# Power_stage.net
KiCad netlist of a schematic drawn in Altium Designer
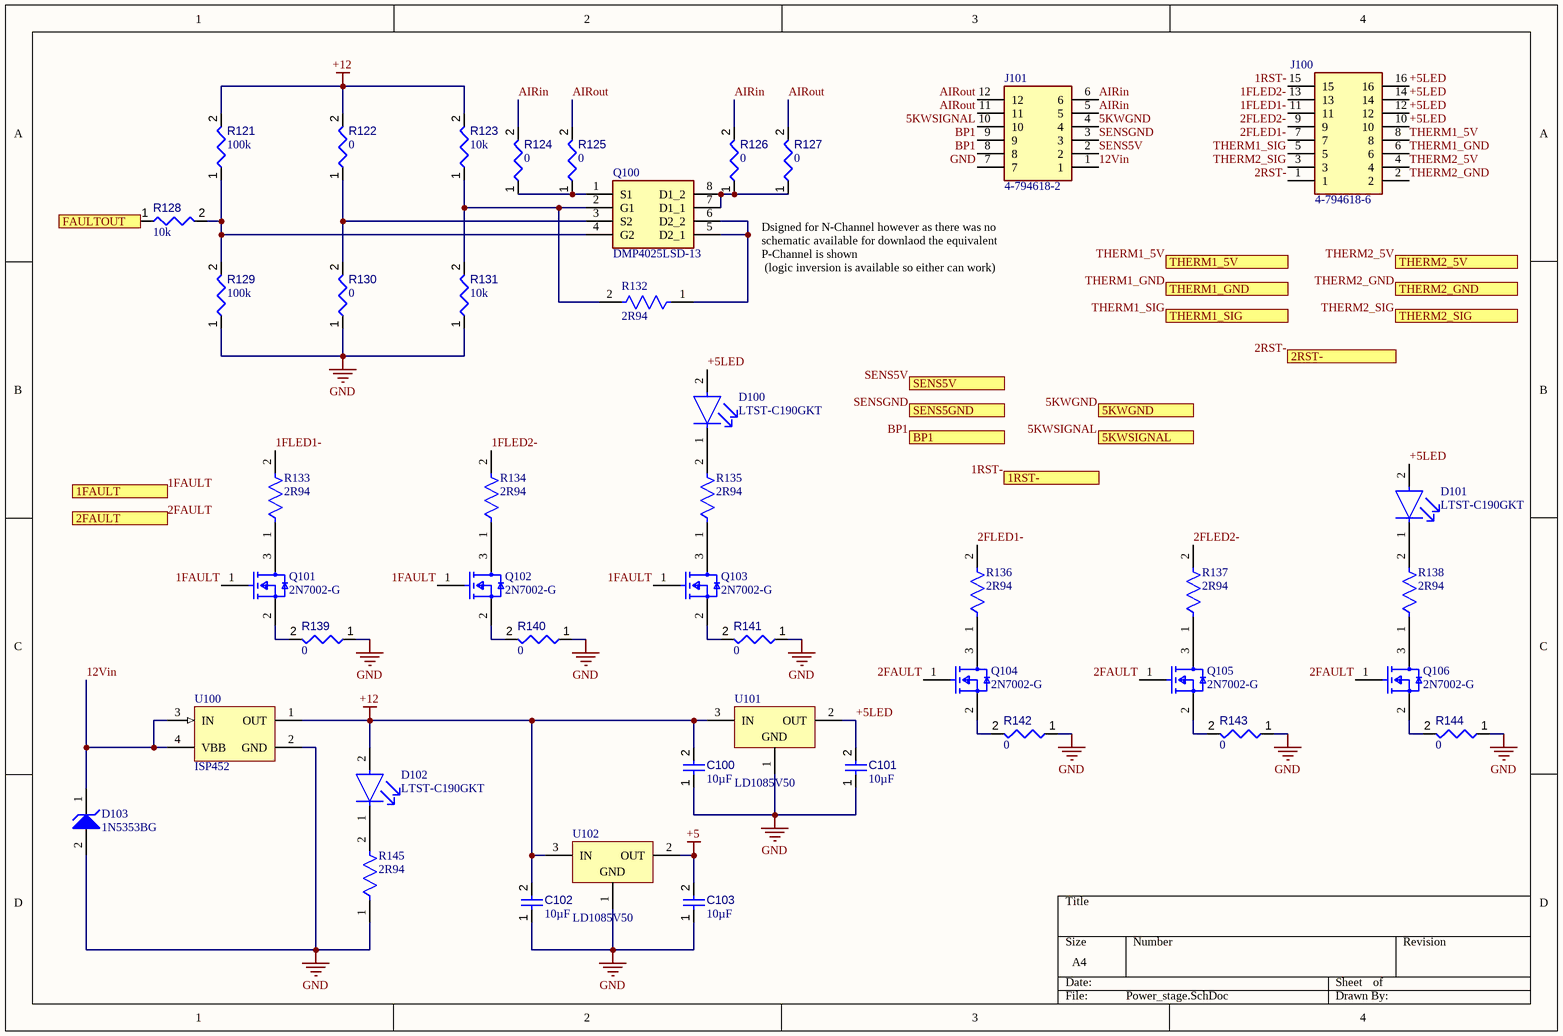
[diagram p0: Power_stage.SchDoc]

(export (version "E")
  (design (tool "Eeschema 10.0.6"))
  (components
    (comp (ref "C100")
      (value "10µF")
      (footprint "CAPC0805(2012)145_L")
      (description "Chip Capacitor, 10µF +/-20%, 25V, 0805, Thickness 1.45 mm")
      (fields (field (name "TOLERANCE") "10%") (field (name "Comment") "Capacitor 10µF +/-20% 25V 0805"))
      (libsource (lib "UNSW Redback Racing") (part "CAP-NP-2"))
    )
    (comp (ref "C101")
      (value "10µF")
      (footprint "CAPC0805(2012)145_L")
      (description "Chip Capacitor, 10µF +/-20%, 25V, 0805, Thickness 1.45 mm")
      (fields (field (name "TOLERANCE") "10%") (field (name "Comment") "Capacitor 10µF +/-20% 25V 0805"))
      (libsource (lib "UNSW Redback Racing") (part "CAP-NP-2"))
    )
    (comp (ref "C102")
      (value "10µF")
      (footprint "CAPC0805(2012)145_L")
      (description "Chip Capacitor, 10µF +/-20%, 25V, 0805, Thickness 1.45 mm")
      (fields (field (name "TOLERANCE") "10%") (field (name "Comment") "Capacitor 10µF +/-20% 25V 0805"))
      (libsource (lib "UNSW Redback Racing") (part "CAP-NP-2"))
    )
    (comp (ref "C103")
      (value "10µF")
      (footprint "CAPC0805(2012)145_L")
      (description "Chip Capacitor, 10µF +/-20%, 25V, 0805, Thickness 1.45 mm")
      (fields (field (name "TOLERANCE") "10%") (field (name "Comment") "Capacitor 10µF +/-20% 25V 0805"))
      (libsource (lib "UNSW Redback Racing") (part "CAP-NP-2"))
    )
    (comp (ref "D100")
      (value "LTST-C190GKT")
      (footprint "FP-LTST-C190GKT-MFG")
      (description "LED GREEN CLEAR CHIP SMD")
      (fields (field (name "VOLTAGE") "2V"))
      (libsource (lib "Altium Content Vault") (part "8706943c75ba83719d021d2fdc84c58"))
    )
    (comp (ref "D101")
      (value "LTST-C190GKT")
      (footprint "FP-LTST-C190GKT-MFG")
      (description "LED GREEN CLEAR CHIP SMD")
      (fields (field (name "VOLTAGE") "2V"))
      (libsource (lib "Altium Content Vault") (part "8706943c75ba83719d021d2fdc84c58"))
    )
    (comp (ref "D102")
      (value "LTST-C190GKT")
      (footprint "FP-LTST-C190GKT-MFG")
      (description "LED GREEN CLEAR CHIP SMD")
      (fields (field (name "VOLTAGE") "2V"))
      (libsource (lib "Altium Content Vault") (part "8706943c75ba83719d021d2fdc84c58"))
    )
    (comp (ref "D103")
      (value "1N5353BG")
      (footprint "ONSC-SURMETIC40-2-017AA-01")
      (description "5 W Zener Voltage Regulator, 2-Pin Surmetic(TM) 40, Pb-Free, Bulk Box")
      (fields (field (name "MANUFACTURER") "On Semiconductor"))
      (libsource (lib "Altium Content Vault") (part "ONSC-K1A2-2"))
    )
    (comp (ref "J100")
      (value "4-794618-6")
      (footprint "SamacSys:47946186")
      (description "Connector")
      (fields (field (name "MOUSER PART NUMBER") "571-4-794618-6"))
      (libsource (lib "*") (part "4-794618-6"))
    )
    (comp (ref "J101")
      (value "4-794618-2")
      (footprint "SamacSys:47946182")
      (description "Connector")
      (fields (field (name "MOUSER PART NUMBER") "571-4-794618-2"))
      (libsource (lib "*") (part "4-794618-2"))
    )
    (comp (ref "Q100")
      (value "DMP4025LSD-13")
      (footprint "SamacSys:SOIC127P600X175-8N")
      (description "MOSFET (P-Channel)")
      (fields (field (name "MOUSER PART NUMBER") "621-DMP4025LSD-13"))
      (libsource (lib "*") (part "DMP4025LSD-13"))
    )
    (comp (ref "Q101")
      (value "2N7002-G")
      (footprint "FP-2N7002-G-IPC_C")
      (description "MOSFET N-CH 60V 0.115A SOT23-3")
      (fields
        (field (name "OCTOPART") "https://octopart.com/2n7002-g-microchip-47153309")
        (field (name "MANUFACTURER") "Microchip")
      )
      (libsource (lib "Altium Content Vault") (part "e719174c72bdd709d73c8feae40c216"))
    )
    (comp (ref "Q102")
      (value "2N7002-G")
      (footprint "FP-2N7002-G-IPC_C")
      (description "MOSFET N-CH 60V 0.115A SOT23-3")
      (fields
        (field (name "OCTOPART") "https://octopart.com/2n7002-g-microchip-47153309")
        (field (name "MANUFACTURER") "Microchip")
      )
      (libsource (lib "Altium Content Vault") (part "e719174c72bdd709d73c8feae40c216"))
    )
    (comp (ref "Q103")
      (value "2N7002-G")
      (footprint "FP-2N7002-G-IPC_C")
      (description "MOSFET N-CH 60V 0.115A SOT23-3")
      (fields
        (field (name "OCTOPART") "https://octopart.com/2n7002-g-microchip-47153309")
        (field (name "MANUFACTURER") "Microchip")
      )
      (libsource (lib "Altium Content Vault") (part "e719174c72bdd709d73c8feae40c216"))
    )
    (comp (ref "Q104")
      (value "2N7002-G")
      (footprint "FP-2N7002-G-IPC_C")
      (description "MOSFET N-CH 60V 0.115A SOT23-3")
      (fields
        (field (name "OCTOPART") "https://octopart.com/2n7002-g-microchip-47153309")
        (field (name "MANUFACTURER") "Microchip")
      )
      (libsource (lib "Altium Content Vault") (part "e719174c72bdd709d73c8feae40c216"))
    )
    (comp (ref "Q105")
      (value "2N7002-G")
      (footprint "FP-2N7002-G-IPC_C")
      (description "MOSFET N-CH 60V 0.115A SOT23-3")
      (fields
        (field (name "OCTOPART") "https://octopart.com/2n7002-g-microchip-47153309")
        (field (name "MANUFACTURER") "Microchip")
      )
      (libsource (lib "Altium Content Vault") (part "e719174c72bdd709d73c8feae40c216"))
    )
    (comp (ref "Q106")
      (value "2N7002-G")
      (footprint "FP-2N7002-G-IPC_C")
      (description "MOSFET N-CH 60V 0.115A SOT23-3")
      (fields
        (field (name "OCTOPART") "https://octopart.com/2n7002-g-microchip-47153309")
        (field (name "MANUFACTURER") "Microchip")
      )
      (libsource (lib "Altium Content Vault") (part "e719174c72bdd709d73c8feae40c216"))
    )
    (comp (ref "R121")
      (value "100k")
      (footprint "RESC1608X55X25ML10T15")
      (description "Chip Resistor, 100 KOhm, +/- 1%, 0.1 W, -55 to 155 degC, 0603 (1608 Metric)")
      (fields (field (name "TOLERANCE") "1%") (field (name "POWER") "100mW"))
      (libsource (lib "UNSW Redback Racing") (part "RES-2"))
    )
    (comp (ref "R122")
      (value "0")
      (footprint "RESC0603(1608)_L")
      (description "Jumper 0603 (1608 Metric)")
      (fields (field (name "Comment") "0R3J"))
      (libsource (lib "UNSW Redback Racing") (part "0R3J"))
    )
    (comp (ref "R123")
      (value "10k")
      (footprint "RESC1608X55X25ML10T15")
      (description "Chip Resistor, 10 KOhm, +/- 1%, 01 W, -55 to 155 degC, 0603 (1608 Metric)")
      (fields (field (name "POWER") "100mW") (field (name "TOLERANCE") "1%"))
      (libsource (lib "UNSW Redback Racing") (part "RES-2"))
    )
    (comp (ref "R124")
      (value "0")
      (footprint "RESC0603(1608)_L")
      (description "Jumper 0603 (1608 Metric)")
      (fields (field (name "Comment") "0R3J"))
      (libsource (lib "UNSW Redback Racing") (part "0R3J"))
    )
    (comp (ref "R125")
      (value "0")
      (footprint "RESC0603(1608)_L")
      (description "Jumper 0603 (1608 Metric)")
      (fields (field (name "Comment") "0R3J"))
      (libsource (lib "UNSW Redback Racing") (part "0R3J"))
    )
    (comp (ref "R126")
      (value "0")
      (footprint "RESC0603(1608)_L")
      (description "Jumper 0603 (1608 Metric)")
      (fields (field (name "Comment") "0R3J"))
      (libsource (lib "UNSW Redback Racing") (part "0R3J"))
    )
    (comp (ref "R127")
      (value "0")
      (footprint "RESC0603(1608)_L")
      (description "Jumper 0603 (1608 Metric)")
      (fields (field (name "Comment") "0R3J"))
      (libsource (lib "UNSW Redback Racing") (part "0R3J"))
    )
    (comp (ref "R128")
      (value "10k")
      (footprint "RESC1608X55X25ML10T15")
      (description "Chip Resistor, 10 KOhm, +/- 1%, 01 W, -55 to 155 degC, 0603 (1608 Metric)")
      (fields (field (name "POWER") "100mW") (field (name "TOLERANCE") "1%"))
      (libsource (lib "UNSW Redback Racing") (part "RES-2"))
    )
    (comp (ref "R129")
      (value "100k")
      (footprint "RESC1608X55X25ML10T15")
      (description "Chip Resistor, 100 KOhm, +/- 1%, 0.1 W, -55 to 155 degC, 0603 (1608 Metric)")
      (fields (field (name "TOLERANCE") "1%") (field (name "POWER") "100mW"))
      (libsource (lib "UNSW Redback Racing") (part "RES-2"))
    )
    (comp (ref "R130")
      (value "0")
      (footprint "RESC0603(1608)_L")
      (description "Jumper 0603 (1608 Metric)")
      (fields (field (name "Comment") "0R3J"))
      (libsource (lib "UNSW Redback Racing") (part "0R3J"))
    )
    (comp (ref "R131")
      (value "10k")
      (footprint "RESC1608X55X25ML10T15")
      (description "Chip Resistor, 10 KOhm, +/- 1%, 01 W, -55 to 155 degC, 0603 (1608 Metric)")
      (fields (field (name "POWER") "100mW") (field (name "TOLERANCE") "1%"))
      (libsource (lib "UNSW Redback Racing") (part "RES-2"))
    )
    (comp (ref "R132")
      (value "2R94")
      (footprint "FP-CPF0603-MFG")
      (description "RES SMD 2.94Ω 1% 1/16W 0603")
      (fields (field (name "MANUFACTURER PART NUMBER") "CPF0603F2R94C1") (field (name "TOLERANCE") "1%"))
      (libsource (lib "Altium Content Vault") (part "1029c3af85768c4190bb7ad29bc67b5"))
    )
    (comp (ref "R133")
      (value "2R94")
      (footprint "FP-CPF0603-MFG")
      (description "RES SMD 2.94Ω 1% 1/16W 0603")
      (fields (field (name "MANUFACTURER PART NUMBER") "CPF0603F2R94C1") (field (name "TOLERANCE") "1%"))
      (libsource (lib "Altium Content Vault") (part "1029c3af85768c4190bb7ad29bc67b5"))
    )
    (comp (ref "R134")
      (value "2R94")
      (footprint "FP-CPF0603-MFG")
      (description "RES SMD 2.94Ω 1% 1/16W 0603")
      (fields (field (name "MANUFACTURER PART NUMBER") "CPF0603F2R94C1") (field (name "TOLERANCE") "1%"))
      (libsource (lib "Altium Content Vault") (part "1029c3af85768c4190bb7ad29bc67b5"))
    )
    (comp (ref "R135")
      (value "2R94")
      (footprint "FP-CPF0603-MFG")
      (description "RES SMD 2.94Ω 1% 1/16W 0603")
      (fields (field (name "MANUFACTURER PART NUMBER") "CPF0603F2R94C1") (field (name "TOLERANCE") "1%"))
      (libsource (lib "Altium Content Vault") (part "1029c3af85768c4190bb7ad29bc67b5"))
    )
    (comp (ref "R136")
      (value "2R94")
      (footprint "FP-CPF0603-MFG")
      (description "RES SMD 2.94Ω 1% 1/16W 0603")
      (fields (field (name "MANUFACTURER PART NUMBER") "CPF0603F2R94C1") (field (name "TOLERANCE") "1%"))
      (libsource (lib "Altium Content Vault") (part "1029c3af85768c4190bb7ad29bc67b5"))
    )
    (comp (ref "R137")
      (value "2R94")
      (footprint "FP-CPF0603-MFG")
      (description "RES SMD 2.94Ω 1% 1/16W 0603")
      (fields (field (name "MANUFACTURER PART NUMBER") "CPF0603F2R94C1") (field (name "TOLERANCE") "1%"))
      (libsource (lib "Altium Content Vault") (part "1029c3af85768c4190bb7ad29bc67b5"))
    )
    (comp (ref "R138")
      (value "2R94")
      (footprint "FP-CPF0603-MFG")
      (description "RES SMD 2.94Ω 1% 1/16W 0603")
      (fields (field (name "MANUFACTURER PART NUMBER") "CPF0603F2R94C1") (field (name "TOLERANCE") "1%"))
      (libsource (lib "Altium Content Vault") (part "1029c3af85768c4190bb7ad29bc67b5"))
    )
    (comp (ref "R139")
      (value "0")
      (footprint "RESC0603(1608)_L")
      (description "Jumper 0603 (1608 Metric)")
      (fields (field (name "Comment") "0R3J"))
      (libsource (lib "UNSW Redback Racing") (part "0R3J"))
    )
    (comp (ref "R140")
      (value "0")
      (footprint "RESC0603(1608)_L")
      (description "Jumper 0603 (1608 Metric)")
      (fields (field (name "Comment") "0R3J"))
      (libsource (lib "UNSW Redback Racing") (part "0R3J"))
    )
    (comp (ref "R141")
      (value "0")
      (footprint "RESC0603(1608)_L")
      (description "Jumper 0603 (1608 Metric)")
      (fields (field (name "Comment") "0R3J"))
      (libsource (lib "UNSW Redback Racing") (part "0R3J"))
    )
    (comp (ref "R142")
      (value "0")
      (footprint "RESC0603(1608)_L")
      (description "Jumper 0603 (1608 Metric)")
      (fields (field (name "Comment") "0R3J"))
      (libsource (lib "UNSW Redback Racing") (part "0R3J"))
    )
    (comp (ref "R143")
      (value "0")
      (footprint "RESC0603(1608)_L")
      (description "Jumper 0603 (1608 Metric)")
      (fields (field (name "Comment") "0R3J"))
      (libsource (lib "UNSW Redback Racing") (part "0R3J"))
    )
    (comp (ref "R144")
      (value "0")
      (footprint "RESC0603(1608)_L")
      (description "Jumper 0603 (1608 Metric)")
      (fields (field (name "Comment") "0R3J"))
      (libsource (lib "UNSW Redback Racing") (part "0R3J"))
    )
    (comp (ref "R145")
      (value "2R94")
      (footprint "FP-CPF0603-MFG")
      (description "RES SMD 2.94Ω 1% 1/16W 0603")
      (fields (field (name "MANUFACTURER PART NUMBER") "CPF0603F2R94C1") (field (name "TOLERANCE") "1%"))
      (libsource (lib "Altium Content Vault") (part "1029c3af85768c4190bb7ad29bc67b5"))
    )
    (comp (ref "U100")
      (value "ISP452")
      (footprint "INF-SOT223_L")
      (fields (field (name "MANUFACTURER") "Infineon"))
      (libsource (lib "Altium Content Vault") (part "INF-ISP452-SOT223-4"))
    )
    (comp (ref "U101")
      (value "LD1085V50")
      (footprint "TO220")
      (description "3A, Low Drop Positive Voltage Regulator, 5V, 3-Pin TO-220")
      (libsource (lib "Altium Content Vault") (part "PM-REG-LD1085-SIL3"))
    )
    (comp (ref "U102")
      (value "LD1085V50")
      (footprint "TO220")
      (description "3A, Low Drop Positive Voltage Regulator, 5V, 3-Pin TO-220")
      (libsource (lib "Altium Content Vault") (part "PM-REG-LD1085-SIL3"))
    )
  )
  (nets
    (net (code "1") (name "+5") (class "Default")
      (node (ref "C103") (pin "2") (pinfunction "2_2") (pintype "passive"))
      (node (ref "U102") (pin "2") (pinfunction "OUT_2") (pintype "power_in"))
    )
    (net (code "2") (name "+12") (class "Default")
      (node (ref "C100") (pin "2") (pinfunction "2_2") (pintype "passive"))
      (node (ref "C102") (pin "2") (pinfunction "2_2") (pintype "passive"))
      (node (ref "D102") (pin "2") (pinfunction "A_2") (pintype "passive"))
      (node (ref "R121") (pin "2") (pinfunction "2_2") (pintype "passive"))
      (node (ref "R122") (pin "2") (pinfunction "2_2") (pintype "passive"))
      (node (ref "R123") (pin "2") (pinfunction "2_2") (pintype "passive"))
      (node (ref "U100") (pin "1") (pinfunction "OUT_1") (pintype "power_in"))
      (node (ref "U101") (pin "3") (pinfunction "IN_3") (pintype "power_in"))
      (node (ref "U102") (pin "3") (pinfunction "IN_3") (pintype "power_in"))
    )
    (net (code "3") (name "/+5LED") (class "Default")
      (node (ref "C101") (pin "2") (pinfunction "2_2") (pintype "passive"))
      (node (ref "D100") (pin "2") (pinfunction "A_2") (pintype "passive"))
      (node (ref "D101") (pin "2") (pinfunction "A_2") (pintype "passive"))
      (node (ref "J100") (pin "10") (pinfunction "10_10") (pintype "passive"))
      (node (ref "J100") (pin "12") (pinfunction "12_12") (pintype "passive"))
      (node (ref "J100") (pin "14") (pinfunction "14_14") (pintype "passive"))
      (node (ref "J100") (pin "16") (pinfunction "16_16") (pintype "passive"))
      (node (ref "U101") (pin "2") (pinfunction "OUT_2") (pintype "power_in"))
    )
    (net (code "4") (name "/1FAULT") (class "Default")
      (node (ref "Q101") (pin "1") (pinfunction "GATE_1") (pintype "passive"))
      (node (ref "Q102") (pin "1") (pinfunction "GATE_1") (pintype "passive"))
      (node (ref "Q103") (pin "1") (pinfunction "GATE_1") (pintype "passive"))
    )
    (net (code "5") (name "/1FLED1-") (class "Default")
      (node (ref "J100") (pin "11") (pinfunction "11_11") (pintype "passive"))
      (node (ref "R133") (pin "2") (pinfunction "2_2") (pintype "passive"))
    )
    (net (code "6") (name "/1FLED2-") (class "Default")
      (node (ref "J100") (pin "13") (pinfunction "13_13") (pintype "passive"))
      (node (ref "R134") (pin "2") (pinfunction "2_2") (pintype "passive"))
    )
    (net (code "7") (name "/1RST-") (class "Default")
      (node (ref "J100") (pin "15") (pinfunction "15_15") (pintype "passive"))
    )
    (net (code "8") (name "/2FAULT") (class "Default")
      (node (ref "Q104") (pin "1") (pinfunction "GATE_1") (pintype "passive"))
      (node (ref "Q105") (pin "1") (pinfunction "GATE_1") (pintype "passive"))
      (node (ref "Q106") (pin "1") (pinfunction "GATE_1") (pintype "passive"))
    )
    (net (code "9") (name "/2FLED1-") (class "Default")
      (node (ref "J100") (pin "7") (pinfunction "7_7") (pintype "passive"))
      (node (ref "R136") (pin "2") (pinfunction "2_2") (pintype "passive"))
    )
    (net (code "10") (name "/2FLED2-") (class "Default")
      (node (ref "J100") (pin "9") (pinfunction "9_9") (pintype "passive"))
      (node (ref "R137") (pin "2") (pinfunction "2_2") (pintype "passive"))
    )
    (net (code "11") (name "/2RST-") (class "Default")
      (node (ref "J100") (pin "1") (pinfunction "1_1") (pintype "passive"))
    )
    (net (code "12") (name "/5KWGND") (class "Default")
      (node (ref "J101") (pin "4") (pinfunction "4_4") (pintype "passive"))
    )
    (net (code "13") (name "/5KWSIGNAL") (class "Default")
      (node (ref "J101") (pin "10") (pinfunction "10_10") (pintype "passive"))
    )
    (net (code "14") (name "/12Vin") (class "Default")
      (node (ref "D103") (pin "1") (pinfunction "K_1") (pintype "passive"))
      (node (ref "J101") (pin "1") (pinfunction "1_1") (pintype "passive"))
      (node (ref "U100") (pin "3") (pinfunction "IN_3") (pintype "input"))
      (node (ref "U100") (pin "4") (pinfunction "VBB_4") (pintype "power_in"))
    )
    (net (code "15") (name "/AIRin") (class "Default")
      (node (ref "J101") (pin "5") (pinfunction "5_5") (pintype "passive"))
      (node (ref "J101") (pin "6") (pinfunction "6_6") (pintype "passive"))
      (node (ref "R124") (pin "2") (pinfunction "2_2") (pintype "passive"))
      (node (ref "R126") (pin "2") (pinfunction "2_2") (pintype "passive"))
    )
    (net (code "16") (name "/AIRout") (class "Default")
      (node (ref "J101") (pin "11") (pinfunction "11_11") (pintype "passive"))
      (node (ref "J101") (pin "12") (pinfunction "12_12") (pintype "passive"))
      (node (ref "R125") (pin "2") (pinfunction "2_2") (pintype "passive"))
      (node (ref "R127") (pin "2") (pinfunction "2_2") (pintype "passive"))
    )
    (net (code "17") (name "/BP1") (class "Default")
      (node (ref "J101") (pin "8") (pinfunction "8_8") (pintype "passive"))
      (node (ref "J101") (pin "9") (pinfunction "9_9") (pintype "passive"))
    )
    (net (code "18") (name "/FAULTOUT") (class "Default")
      (node (ref "R128") (pin "1") (pinfunction "1_1") (pintype "passive"))
    )
    (net (code "20") (name "/SENS5V") (class "Default")
      (node (ref "J101") (pin "2") (pinfunction "2_2") (pintype "passive"))
    )
    (net (code "21") (name "/SENSGND") (class "Default")
      (node (ref "J101") (pin "3") (pinfunction "3_3") (pintype "passive"))
    )
    (net (code "22") (name "/THERM1_5V") (class "Default")
      (node (ref "J100") (pin "8") (pinfunction "8_8") (pintype "passive"))
    )
    (net (code "23") (name "/THERM1_GND") (class "Default")
      (node (ref "J100") (pin "6") (pinfunction "6_6") (pintype "passive"))
    )
    (net (code "24") (name "/THERM1_SIG") (class "Default")
      (node (ref "J100") (pin "5") (pinfunction "5_5") (pintype "passive"))
    )
    (net (code "25") (name "/THERM2_5V") (class "Default")
      (node (ref "J100") (pin "4") (pinfunction "4_4") (pintype "passive"))
    )
    (net (code "26") (name "/THERM2_GND") (class "Default")
      (node (ref "J100") (pin "2") (pinfunction "2_2") (pintype "passive"))
    )
    (net (code "27") (name "/THERM2_SIG") (class "Default")
      (node (ref "J100") (pin "3") (pinfunction "3_3") (pintype "passive"))
    )
    (net (code "28") (name "GND") (class "Default")
      (node (ref "C100") (pin "1") (pinfunction "1_1") (pintype "passive"))
      (node (ref "C101") (pin "1") (pinfunction "1_1") (pintype "passive"))
      (node (ref "C102") (pin "1") (pinfunction "1_1") (pintype "passive"))
      (node (ref "C103") (pin "1") (pinfunction "1_1") (pintype "passive"))
      (node (ref "D103") (pin "2") (pinfunction "A_2") (pintype "passive"))
      (node (ref "J101") (pin "7") (pinfunction "7_7") (pintype "passive"))
      (node (ref "R129") (pin "1") (pinfunction "1_1") (pintype "passive"))
      (node (ref "R130") (pin "1") (pinfunction "1_1") (pintype "passive"))
      (node (ref "R131") (pin "1") (pinfunction "1_1") (pintype "passive"))
      (node (ref "R139") (pin "1") (pinfunction "1_1") (pintype "passive"))
      (node (ref "R140") (pin "1") (pinfunction "1_1") (pintype "passive"))
      (node (ref "R141") (pin "1") (pinfunction "1_1") (pintype "passive"))
      (node (ref "R142") (pin "1") (pinfunction "1_1") (pintype "passive"))
      (node (ref "R143") (pin "1") (pinfunction "1_1") (pintype "passive"))
      (node (ref "R144") (pin "1") (pinfunction "1_1") (pintype "passive"))
      (node (ref "R145") (pin "1") (pinfunction "1_1") (pintype "passive"))
      (node (ref "U100") (pin "2") (pinfunction "GND_2") (pintype "power_in"))
      (node (ref "U101") (pin "1") (pinfunction "GND_1") (pintype "power_in"))
      (node (ref "U102") (pin "1") (pinfunction "GND_1") (pintype "power_in"))
    )
    (net (code "29") (name "Net-(D100-C)") (class "Default")
      (node (ref "D100") (pin "1") (pinfunction "C_1") (pintype "passive"))
      (node (ref "R135") (pin "2") (pinfunction "2_2") (pintype "passive"))
    )
    (net (code "30") (name "Net-(D101-C)") (class "Default")
      (node (ref "D101") (pin "1") (pinfunction "C_1") (pintype "passive"))
      (node (ref "R138") (pin "2") (pinfunction "2_2") (pintype "passive"))
    )
    (net (code "31") (name "Net-(D102-C)") (class "Default")
      (node (ref "D102") (pin "1") (pinfunction "C_1") (pintype "passive"))
      (node (ref "R145") (pin "2") (pinfunction "2_2") (pintype "passive"))
    )
    (net (code "32") (name "Net-(Q100-D1_1)") (class "Default")
      (node (ref "Q100") (pin "7") (pinfunction "D1_1_7") (pintype "passive"))
      (node (ref "Q100") (pin "8") (pinfunction "D1_2_8") (pintype "passive"))
      (node (ref "R126") (pin "1") (pinfunction "1_1") (pintype "passive"))
      (node (ref "R127") (pin "1") (pinfunction "1_1") (pintype "passive"))
    )
    (net (code "33") (name "Net-(Q100-D2_1)") (class "Default")
      (node (ref "Q100") (pin "5") (pinfunction "D2_1_5") (pintype "passive"))
      (node (ref "Q100") (pin "6") (pinfunction "D2_2_6") (pintype "passive"))
      (node (ref "R132") (pin "1") (pinfunction "1_1") (pintype "passive"))
    )
    (net (code "34") (name "Net-(Q100-G1)") (class "Default")
      (node (ref "Q100") (pin "2") (pinfunction "G1_2") (pintype "passive"))
      (node (ref "R123") (pin "1") (pinfunction "1_1") (pintype "passive"))
      (node (ref "R131") (pin "2") (pinfunction "2_2") (pintype "passive"))
      (node (ref "R132") (pin "2") (pinfunction "2_2") (pintype "passive"))
    )
    (net (code "35") (name "Net-(Q100-G2)") (class "Default")
      (node (ref "Q100") (pin "4") (pinfunction "G2_4") (pintype "passive"))
      (node (ref "R121") (pin "1") (pinfunction "1_1") (pintype "passive"))
      (node (ref "R128") (pin "2") (pinfunction "2_2") (pintype "passive"))
      (node (ref "R129") (pin "2") (pinfunction "2_2") (pintype "passive"))
    )
    (net (code "36") (name "Net-(Q100-S1)") (class "Default")
      (node (ref "Q100") (pin "1") (pinfunction "S1_1") (pintype "passive"))
      (node (ref "R124") (pin "1") (pinfunction "1_1") (pintype "passive"))
      (node (ref "R125") (pin "1") (pinfunction "1_1") (pintype "passive"))
    )
    (net (code "37") (name "Net-(Q100-S2)") (class "Default")
      (node (ref "Q100") (pin "3") (pinfunction "S2_3") (pintype "passive"))
      (node (ref "R122") (pin "1") (pinfunction "1_1") (pintype "passive"))
      (node (ref "R130") (pin "2") (pinfunction "2_2") (pintype "passive"))
    )
    (net (code "38") (name "Net-(Q101-DRAIN)") (class "Default")
      (node (ref "Q101") (pin "3") (pinfunction "DRAIN_3") (pintype "passive"))
      (node (ref "R133") (pin "1") (pinfunction "1_1") (pintype "passive"))
    )
    (net (code "39") (name "Net-(Q101-SOURCE)") (class "Default")
      (node (ref "Q101") (pin "2") (pinfunction "SOURCE_2") (pintype "passive"))
      (node (ref "R139") (pin "2") (pinfunction "2_2") (pintype "passive"))
    )
    (net (code "40") (name "Net-(Q102-DRAIN)") (class "Default")
      (node (ref "Q102") (pin "3") (pinfunction "DRAIN_3") (pintype "passive"))
      (node (ref "R134") (pin "1") (pinfunction "1_1") (pintype "passive"))
    )
    (net (code "41") (name "Net-(Q102-SOURCE)") (class "Default")
      (node (ref "Q102") (pin "2") (pinfunction "SOURCE_2") (pintype "passive"))
      (node (ref "R140") (pin "2") (pinfunction "2_2") (pintype "passive"))
    )
    (net (code "42") (name "Net-(Q103-DRAIN)") (class "Default")
      (node (ref "Q103") (pin "3") (pinfunction "DRAIN_3") (pintype "passive"))
      (node (ref "R135") (pin "1") (pinfunction "1_1") (pintype "passive"))
    )
    (net (code "43") (name "Net-(Q103-SOURCE)") (class "Default")
      (node (ref "Q103") (pin "2") (pinfunction "SOURCE_2") (pintype "passive"))
      (node (ref "R141") (pin "2") (pinfunction "2_2") (pintype "passive"))
    )
    (net (code "44") (name "Net-(Q104-DRAIN)") (class "Default")
      (node (ref "Q104") (pin "3") (pinfunction "DRAIN_3") (pintype "passive"))
      (node (ref "R136") (pin "1") (pinfunction "1_1") (pintype "passive"))
    )
    (net (code "45") (name "Net-(Q104-SOURCE)") (class "Default")
      (node (ref "Q104") (pin "2") (pinfunction "SOURCE_2") (pintype "passive"))
      (node (ref "R142") (pin "2") (pinfunction "2_2") (pintype "passive"))
    )
    (net (code "46") (name "Net-(Q105-DRAIN)") (class "Default")
      (node (ref "Q105") (pin "3") (pinfunction "DRAIN_3") (pintype "passive"))
      (node (ref "R137") (pin "1") (pinfunction "1_1") (pintype "passive"))
    )
    (net (code "47") (name "Net-(Q105-SOURCE)") (class "Default")
      (node (ref "Q105") (pin "2") (pinfunction "SOURCE_2") (pintype "passive"))
      (node (ref "R143") (pin "2") (pinfunction "2_2") (pintype "passive"))
    )
    (net (code "48") (name "Net-(Q106-DRAIN)") (class "Default")
      (node (ref "Q106") (pin "3") (pinfunction "DRAIN_3") (pintype "passive"))
      (node (ref "R138") (pin "1") (pinfunction "1_1") (pintype "passive"))
    )
    (net (code "49") (name "Net-(Q106-SOURCE)") (class "Default")
      (node (ref "Q106") (pin "2") (pinfunction "SOURCE_2") (pintype "passive"))
      (node (ref "R144") (pin "2") (pinfunction "2_2") (pintype "passive"))
    )
  )
)
